# AFE_Channel_3.net
KiCad netlist of a schematic drawn in Altium Designer
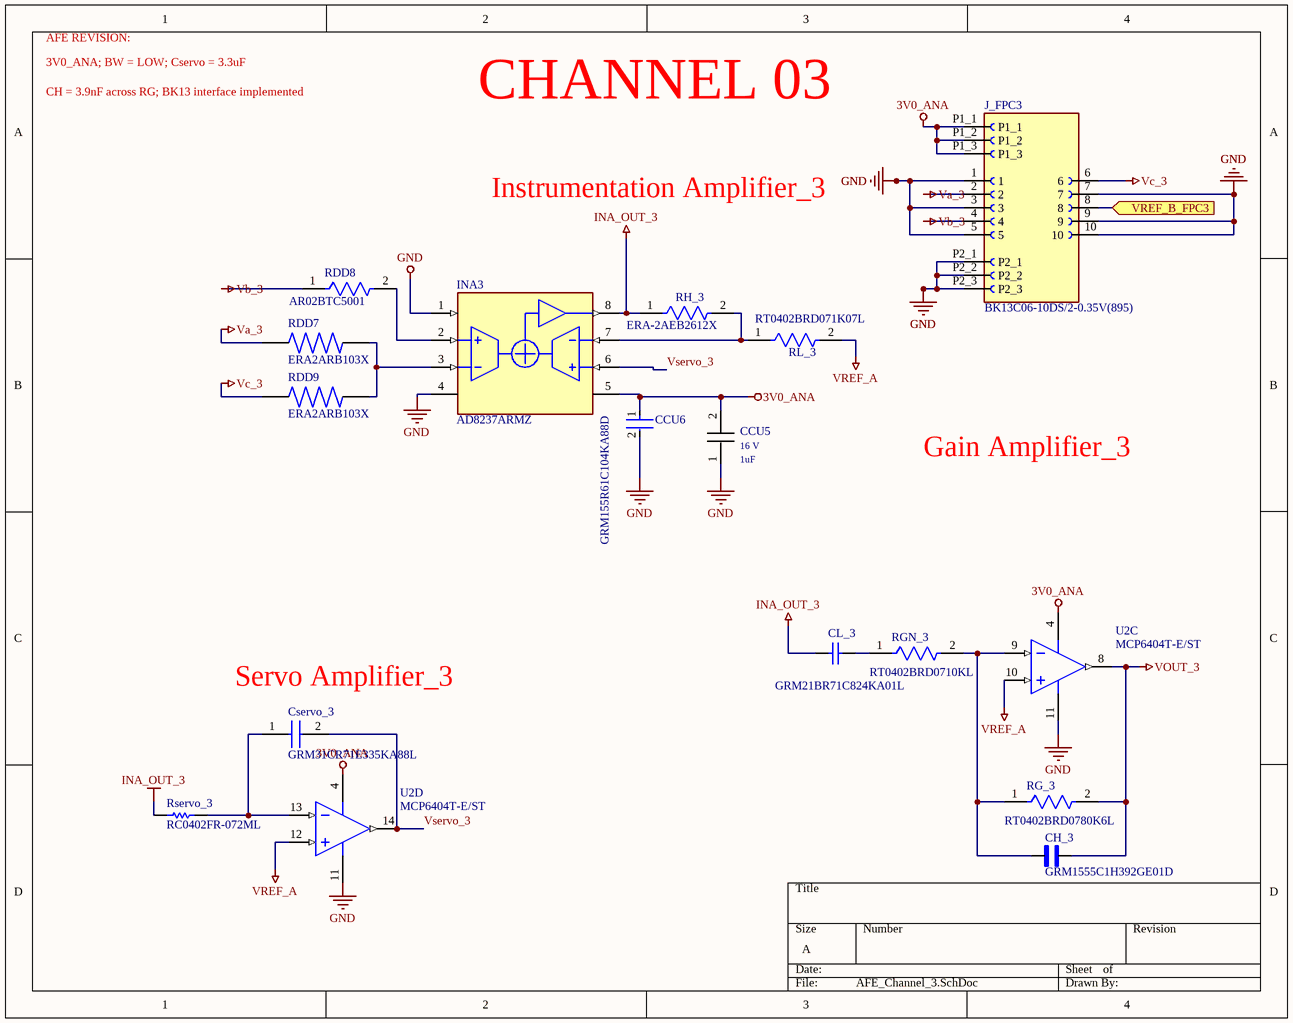
[diagram p0: AFE_Channel_3.SchDoc]

(export (version "E")
  (design (tool "Eeschema 10.0.6"))
  (components
    (comp (ref "CCU5")
      (value "MURATA_GRM155C71C105KE11D")
      (footprint "MURATA_GRM155C71C105KE11D_0:*MURATA_GRM155C71C105KE11D_0")
      (description "Murata GRM155C71C105KE11D: 1 uF 16 V X7S +/-10%, 0402/1005 metric")
      (fields (field (name "MF") "Murata") (field (name "MP") "GRM155C71C105KE11D"))
      (libsource (lib "EMG_Controlled_R5") (part "EMG_R5_CCU5"))
    )
    (comp (ref "CCU6")
      (value "GRM155R61C104KA88D")
      (footprint "96DF66F8-B997-472F-A885-42BCAAE661B2_FP-GRM155-0_05-IPC_C:FP-GRM155-0_05-IPC_C")
      (description "CAP CER 0.1UF 16V X5R 0402")
      (fields (field (name "VOLTAGE") "16V") (field (name "TOLERANCE") "10%"))
      (libsource (lib "EMG_Controlled_R5") (part "EMG_R5_CCU6"))
    )
    (comp (ref "CH_3")
      (value "GRM1555C1H392GE01D")
      (footprint "GRM1555C1H392GE01D_0:CAPC1005X55N")
      (description "SMD capacitor C0G(EIA) with capacitance 3900pF Tol.2%. Rated voltage 50Vdc 125C")
      (fields (field (name "MF") "Murata Electronics"))
      (libsource (lib "EMG_Controlled_R5") (part "EMG_R5_CH_3"))
    )
    (comp (ref "CL_3")
      (value "GRM21BR71C824KA01L")
      (footprint "987105EF-01FA-4198-A59F-44D3B68BB40E_CAPC2013X135X45ML10T25:CAPC2013X135X45ML10T25")
      (fields (field (name "MANUFACTURER") "Murata"))
      (libsource (lib "EMG_Controlled_R5") (part "EMG_R5_CL_3"))
    )
    (comp (ref "Cservo_3")
      (value "GRM31CR71E335KA88L")
      (footprint "SamacSys:GRM31x")
      (description "Capacitor")
      (fields
        (field (name "MOUSER PART NUMBER") "81-GRM31CR71E335KA8L")
        (field (name "MANUFACTURER") "Murata")
      )
      (libsource (lib "EMG_Controlled_R5") (part "EMG_R5_Cservo_3"))
    )
    (comp (ref "INA3")
      (value "AD8237ARMZ")
      (footprint "EMG_AD8237_R3:EMG_AD8237_R3_MSOP8")
      (description "Micropower, Zero Drift, True Rail-to-Rail Instrumentation Amplifier")
      (fields (field (name "MF") "Analog Devices"))
      (libsource (lib "EMG_Controlled_R5") (part "EMG_R5_INA3"))
    )
    (comp (ref "J_FPC3")
      (value "BK13C06-10DS/2-0.35V(895)")
      (footprint "BK13C06-10DS_2-0.35V_895__0:HIROSE_BK13C06-10DS/2-0.35V(895)")
      (description "10 Position Connector Receptacle, Center Strip Contacts Surface Mount Gold")
      (fields (field (name "MF") "Hirose Electric Co Ltd"))
      (libsource (lib "EMG_Controlled_R5") (part "EMG_R5_J_FPC3"))
    )
    (comp (ref "RDD7")
      (value "ERA2ARB103X")
      (footprint "ERA2ARB103X_0:RES_ERA2ARB103X")
      (libsource (lib "EMG_Controlled_R5") (part "EMG_R5_RDD7"))
    )
    (comp (ref "RDD8")
      (value "AR02BTC5001")
      (footprint "7D606042-220B-45EE-95DD-CA1A974E4C0D_FP-AC0402-MFG:FP-AC0402-MFG")
      (description "-55℃~+155℃ 50V 5kΩ 63mW Thin Film Resistor ±0.1% ±25ppm/℃ 0402 Chip Resistor - Surface Mount ROH")
      (fields
        (field (name "MANUFACTURER") "Viking Tech")
        (field (name "OCTOPART") "https://octopart.com/datasheet/viking-tech/AR02BTC5001")
      )
      (libsource (lib "EMG_Controlled_R5") (part "EMG_R5_RDD8"))
    )
    (comp (ref "RDD9")
      (value "ERA2ARB103X")
      (footprint "ERA2ARB103X_0:RES_ERA2ARB103X")
      (libsource (lib "EMG_Controlled_R5") (part "EMG_R5_RDD9"))
    )
    (comp (ref "RGN_3")
      (value "RT0402BRD0710KL")
      (footprint "B876F212-A29A-4983-9BB8-539D1BA2EBA1_FP-RT0402-MFG:FP-RT0402-MFG")
      (description "RES 10.0K OHM 1/16W .1% SMD 0402")
      (fields
        (field (name "MANUFACTURER") "Yageo")
        (field (name "OCTOPART") "https://octopart.com/rt0402brd0710kl-yageo-1181432")
      )
      (libsource (lib "EMG_Controlled_R5") (part "EMG_R5_RGN_3"))
    )
    (comp (ref "RG_3")
      (value "RT0402BRD0780K6L")
      (footprint "B876F212-A29A-4983-9BB8-539D1BA2EBA1_FP-RT0402-MFG:FP-RT0402-MFG")
      (description "RES SMD 80.6KOHM 0.1% 1/16W 0402")
      (fields
        (field (name "MANUFACTURER") "Yageo")
        (field (name "OCTOPART") "https://octopart.com/rt0402brd0780k6l-yageo-1468076")
      )
      (libsource (lib "EMG_Controlled_R5") (part "EMG_R5_RG_3"))
    )
    (comp (ref "RH_3")
      (value "ERA-2AEB2612X")
      (footprint "1CBBEC27-AD79-48E8-A701-2E235EA9F8F2_FP-AC0402-IPC_A:FP-AC0402-IPC_A")
      (description "RES 26.1kΩ ±0.1% 0.063W 0402")
      (fields (field (name "TOLERANCE") "0.1%") (field (name "MANUFACTURER") "PANASONIC"))
      (libsource (lib "EMG_Controlled_R5") (part "EMG_R5_RH_3"))
    )
    (comp (ref "RL_3")
      (value "RT0402BRD071K07L")
      (footprint "B876F212-A29A-4983-9BB8-539D1BA2EBA1_FP-RT0402-MFG:FP-RT0402-MFG")
      (description "RES SMD 1.07K OHM 0.1% 1/16W")
      (fields
        (field (name "OCTOPART") "https://octopart.com/rt0402brd071k07l-yageo-1400807")
        (field (name "MANUFACTURER") "Yageo")
      )
      (libsource (lib "EMG_Controlled_R5") (part "EMG_R5_RL_3"))
    )
    (comp (ref "Rservo_3")
      (value "RC0402FR-072ML")
      (footprint "3EB15388-1759-44FF-BAE1-1F0823F3E8F1_RESC1005X40X25NL05T10:RESC1005X40X25NL05T10")
      (fields (field (name "MANUFACTURER") "Yageo / Phycomp"))
      (libsource (lib "EMG_Controlled_R5") (part "EMG_R5_Rservo_3"))
    )
    (comp (ref "U2")
      (value "MCP6404T-E/ST")
      (footprint "CEF93338-31F0-4C64-85B6-F650E0BB75E3_TSSOP-ST14_N:TSSOP-ST14_N")
      (description "None")
      (libsource (lib "EMG_Controlled_R5") (part "EMG_R5_U2"))
    )
  )
  (nets
    (net (code "1") (name "/VREF_B_FPC3") (class "Default")
      (node (ref "J_FPC3") (pin "8") (pinfunction "8_8") (pintype "passive"))
    )
    (net (code "2") (name "/Vservo_3") (class "Default")
      (node (ref "Cservo_3") (pin "2") (pinfunction "2_2") (pintype "passive"))
      (node (ref "INA3") (pin "6") (pinfunction "REF_6") (pintype "input"))
      (node (ref "U2") (pin "14") (pinfunction "VOUTD_14") (pintype "output"))
    )
    (net (code "3") (name "3V0_ANA") (class "Default")
      (node (ref "CCU5") (pin "2") (pinfunction "2_2") (pintype "passive"))
      (node (ref "CCU6") (pin "1") (pinfunction "1_1") (pintype "passive"))
      (node (ref "INA3") (pin "5") (pinfunction "+VS_5") (pintype "power_in"))
      (node (ref "J_FPC3") (pin "P1_1") (pinfunction "P1_1_P1_1") (pintype "power_in"))
      (node (ref "J_FPC3") (pin "P1_2") (pinfunction "P1_2_P1_2") (pintype "power_in"))
      (node (ref "J_FPC3") (pin "P1_3") (pinfunction "P1_3_P1_3") (pintype "power_in"))
      (node (ref "U2") (pin "4") (pinfunction "VDD_4") (pintype "power_in"))
    )
    (net (code "4") (name "GND") (class "Default")
      (node (ref "CCU5") (pin "1") (pinfunction "1_1") (pintype "passive"))
      (node (ref "CCU6") (pin "2") (pinfunction "2_2") (pintype "passive"))
      (node (ref "INA3") (pin "1") (pinfunction "BW_1") (pintype "input"))
      (node (ref "INA3") (pin "4") (pinfunction "-VS_4") (pintype "power_in"))
      (node (ref "J_FPC3") (pin "1") (pinfunction "1_1") (pintype "passive"))
      (node (ref "J_FPC3") (pin "10") (pinfunction "10_10") (pintype "passive"))
      (node (ref "J_FPC3") (pin "3") (pinfunction "3_3") (pintype "passive"))
      (node (ref "J_FPC3") (pin "5") (pinfunction "5_5") (pintype "passive"))
      (node (ref "J_FPC3") (pin "7") (pinfunction "7_7") (pintype "passive"))
      (node (ref "J_FPC3") (pin "9") (pinfunction "9_9") (pintype "passive"))
      (node (ref "J_FPC3") (pin "P2_1") (pinfunction "P2_1_P2_1") (pintype "power_in"))
      (node (ref "J_FPC3") (pin "P2_2") (pinfunction "P2_2_P2_2") (pintype "power_in"))
      (node (ref "J_FPC3") (pin "P2_3") (pinfunction "P2_3_P2_3") (pintype "power_in"))
      (node (ref "U2") (pin "11") (pinfunction "VSS_11") (pintype "power_in"))
    )
    (net (code "5") (name "INA_OUT_3") (class "Default")
      (node (ref "CL_3") (pin "2") (pinfunction "2_2") (pintype "passive"))
      (node (ref "INA3") (pin "8") (pinfunction "VOUT_8") (pintype "output"))
      (node (ref "RH_3") (pin "1") (pinfunction "1_1") (pintype "passive"))
      (node (ref "Rservo_3") (pin "2") (pinfunction "2_2") (pintype "passive"))
    )
    (net (code "6") (name "Net-(CL_3-Pad1)") (class "Default")
      (node (ref "CL_3") (pin "1") (pinfunction "1_1") (pintype "passive"))
      (node (ref "RGN_3") (pin "1") (pinfunction "1_1") (pintype "passive"))
    )
    (net (code "7") (name "Net-(INA3-+IN)") (class "Default")
      (node (ref "INA3") (pin "2") (pinfunction "+IN_2") (pintype "input"))
      (node (ref "RDD8") (pin "2") (pinfunction "2_2") (pintype "passive"))
    )
    (net (code "8") (name "Net-(INA3--IN)") (class "Default")
      (node (ref "INA3") (pin "3") (pinfunction "-IN_3") (pintype "input"))
      (node (ref "RDD7") (pin "2") (pinfunction "2_2") (pintype "passive"))
      (node (ref "RDD9") (pin "2") (pinfunction "2_2") (pintype "passive"))
    )
    (net (code "9") (name "Net-(INA3-FB)") (class "Default")
      (node (ref "INA3") (pin "7") (pinfunction "FB_7") (pintype "input"))
      (node (ref "RH_3") (pin "2") (pinfunction "2_2") (pintype "passive"))
      (node (ref "RL_3") (pin "1") (pinfunction "1_1") (pintype "passive"))
    )
    (net (code "10") (name "Net-(U2C-VINC-)") (class "Default")
      (node (ref "CH_3") (pin "2") (pinfunction "2_2") (pintype "passive"))
      (node (ref "RGN_3") (pin "2") (pinfunction "2_2") (pintype "passive"))
      (node (ref "RG_3") (pin "1") (pinfunction "1_1") (pintype "passive"))
      (node (ref "U2") (pin "9") (pinfunction "VINC-_9") (pintype "input"))
    )
    (net (code "11") (name "Net-(U2D-VIND-)") (class "Default")
      (node (ref "Cservo_3") (pin "1") (pinfunction "1_1") (pintype "passive"))
      (node (ref "Rservo_3") (pin "1") (pinfunction "1_1") (pintype "passive"))
      (node (ref "U2") (pin "13") (pinfunction "VIND-_13") (pintype "input"))
    )
    (net (code "12") (name "VOUT_3") (class "Default")
      (node (ref "CH_3") (pin "1") (pinfunction "1_1") (pintype "passive"))
      (node (ref "RG_3") (pin "2") (pinfunction "2_2") (pintype "passive"))
      (node (ref "U2") (pin "8") (pinfunction "VOUTC_8") (pintype "output"))
    )
    (net (code "13") (name "VREF_A") (class "Default")
      (node (ref "RL_3") (pin "2") (pinfunction "2_2") (pintype "passive"))
      (node (ref "U2") (pin "10") (pinfunction "VINC+_10") (pintype "input"))
      (node (ref "U2") (pin "12") (pinfunction "VIND+_12") (pintype "input"))
    )
    (net (code "14") (name "Va_3") (class "Default")
      (node (ref "J_FPC3") (pin "2") (pinfunction "2_2") (pintype "passive"))
      (node (ref "RDD7") (pin "1") (pinfunction "1_1") (pintype "passive"))
    )
    (net (code "15") (name "Vb_3") (class "Default")
      (node (ref "J_FPC3") (pin "4") (pinfunction "4_4") (pintype "passive"))
      (node (ref "RDD8") (pin "1") (pinfunction "1_1") (pintype "passive"))
    )
    (net (code "16") (name "Vc_3") (class "Default")
      (node (ref "J_FPC3") (pin "6") (pinfunction "6_6") (pintype "passive"))
      (node (ref "RDD9") (pin "1") (pinfunction "1_1") (pintype "passive"))
    )
  )
)
